# TMC2660_driver.net
KiCad netlist of a schematic drawn in Altium Designer
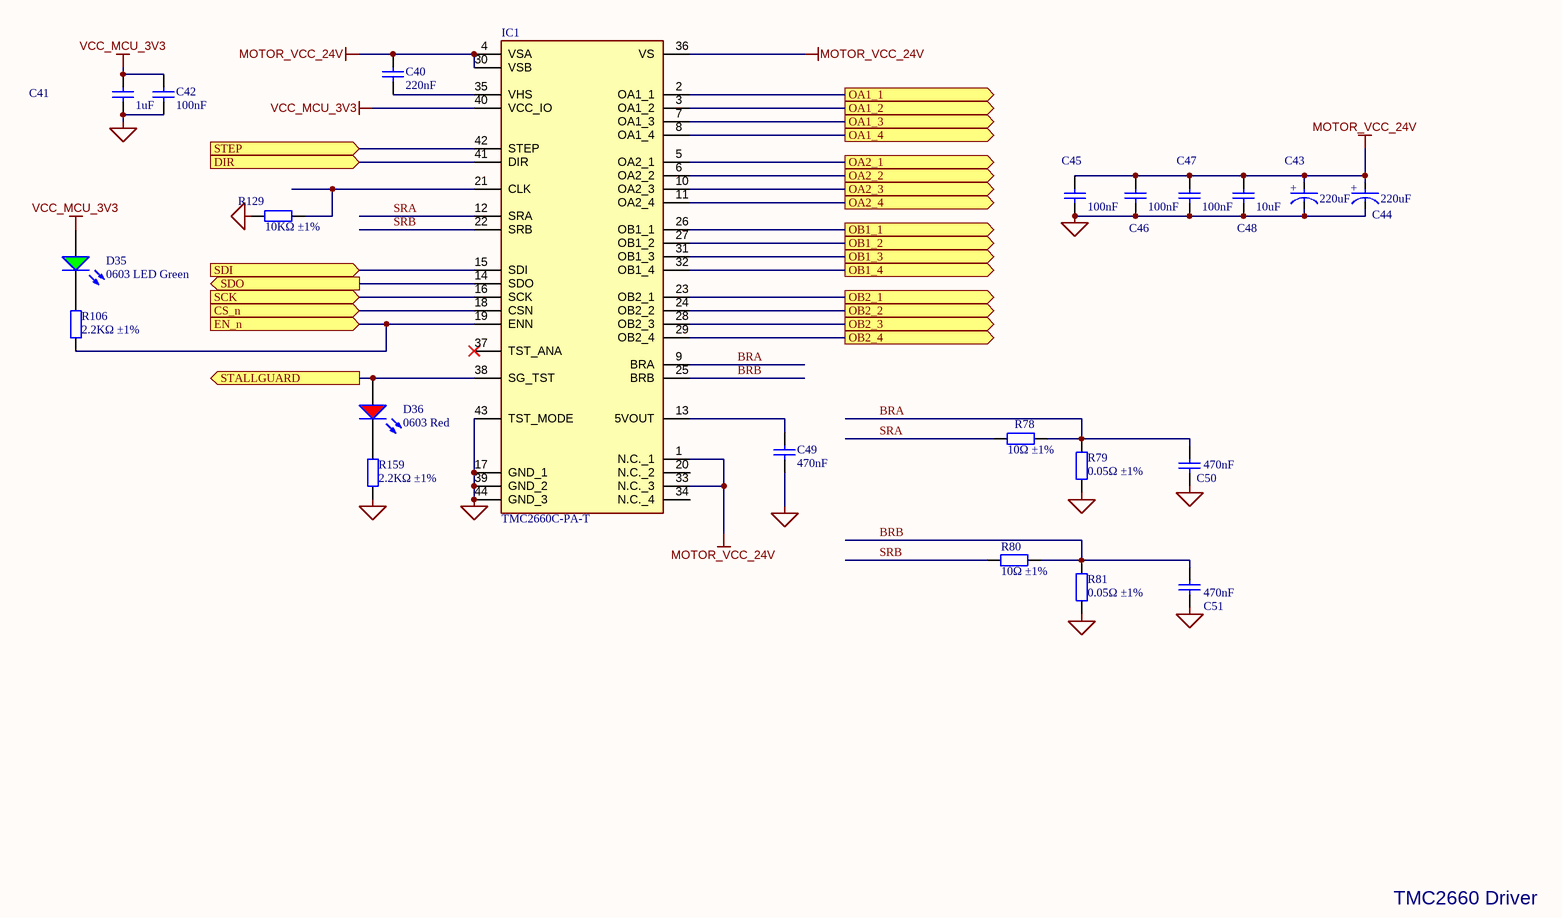
[diagram p0: TMC2660_driver.SchDoc]

(export (version "E")
  (design (tool "Eeschema 10.0.6"))
  (components
    (comp (ref "C40")
      (value "220nF")
      (footprint "0603_C")
      (description "Chip capacitors")
      (fields
        (field (name "MANUFACTURER") "Samsung Electro-Mechanics")
        (field (name "MANUFACTURER PART NUMBER") "CL10B224KA8NNNC")
      )
      (libsource (lib "Cap") (part "0603 220nF (224) 10% 25V"))
    )
    (comp (ref "C41")
      (value "1uF")
      (footprint "0603_C")
      (description "Chip capacitors")
      (fields
        (field (name "MANUFACTURER") "Samsung Electro-Mechanics")
        (field (name "MANUFACTURER PART NUMBER") "CL10A105KB8NNNC")
      )
      (libsource (lib "Cap") (part "0603 1uF (105) 10% 50V"))
    )
    (comp (ref "C42")
      (value "100nF")
      (footprint "0603_C")
      (description "50V 100nF X7R ±10% 0603 Multilayer Ceramic Capacitors MLCC - SMD/SMT ROHS")
      (fields
        (field (name "MANUFACTURER") "YAGEO")
        (field (name "MANUFACTURER PART NUMBER") "CC0603KRX7R9BB104")
      )
      (libsource (lib "Sienci_Labs") (part "0603 100nF (104) 10% 50V"))
    )
    (comp (ref "C43")
      (value "220uF")
      (footprint "FP-FKG-MFG")
      (description "CAP ALUM 220UF 20% 50V SMD")
      (fields (field (name "TOLERANCE") "20%") (field (name "MANUFACTURER") "Nichicon"))
      (libsource (lib "Universal_CNC_Breakout") (part "UUD1H221MNL1GS"))
    )
    (comp (ref "C44")
      (value "220uF")
      (footprint "FP-FKG-MFG")
      (description "CAP ALUM 220UF 20% 50V SMD")
      (fields (field (name "TOLERANCE") "20%") (field (name "MANUFACTURER") "Nichicon"))
      (libsource (lib "Universal_CNC_Breakout") (part "UUD1H221MNL1GS"))
    )
    (comp (ref "C45")
      (value "100nF")
      (footprint "0603_C")
      (description "50V 100nF X7R ±10% 0603 Multilayer Ceramic Capacitors MLCC - SMD/SMT ROHS")
      (fields
        (field (name "MANUFACTURER") "YAGEO")
        (field (name "MANUFACTURER PART NUMBER") "CC0603KRX7R9BB104")
      )
      (libsource (lib "Sienci_Labs") (part "0603 100nF (104) 10% 50V"))
    )
    (comp (ref "C46")
      (value "100nF")
      (footprint "0603_C")
      (description "50V 100nF X7R ±10% 0603 Multilayer Ceramic Capacitors MLCC - SMD/SMT ROHS")
      (fields
        (field (name "MANUFACTURER") "YAGEO")
        (field (name "MANUFACTURER PART NUMBER") "CC0603KRX7R9BB104")
      )
      (libsource (lib "Sienci_Labs") (part "0603 100nF (104) 10% 50V"))
    )
    (comp (ref "C47")
      (value "100nF")
      (footprint "0603_C")
      (description "50V 100nF X7R ±10% 0603 Multilayer Ceramic Capacitors MLCC - SMD/SMT ROHS")
      (fields
        (field (name "MANUFACTURER") "YAGEO")
        (field (name "MANUFACTURER PART NUMBER") "CC0603KRX7R9BB104")
      )
      (libsource (lib "Sienci_Labs") (part "0603 100nF (104) 10% 50V"))
    )
    (comp (ref "C48")
      (value "10uF")
      (footprint "0805_C")
      (description "Chip capacitors")
      (fields
        (field (name "MANUFACTURER") "Samsung Electro-Mechanics")
        (field (name "MANUFACTURER PART NUMBER") "CL21A106KAYNNNE")
      )
      (libsource (lib "Cap") (part "0805 10uF (106) 10% 25V"))
    )
    (comp (ref "C49")
      (value "470nF")
      (footprint "0603_C")
      (description "Chip capacitors")
      (fields
        (field (name "MANUFACTURER") "Samsung Electro-Mechanics")
        (field (name "MANUFACTURER PART NUMBER") "CL10B474KA8NNNC")
      )
      (libsource (lib "Cap") (part "0603 470nF (474) 10% 25V"))
    )
    (comp (ref "C50")
      (value "470nF")
      (footprint "0603_C")
      (description "Chip capacitors")
      (fields (field (name "MANUFACTURER") "Samsung Electro-Mechanics") (field (name "TOLERANCE") "10%"))
      (libsource (lib "Sienci_Labs") (part "0603 470nF (474) 10% 25V"))
    )
    (comp (ref "C51")
      (value "470nF")
      (footprint "0603_C")
      (description "Chip capacitors")
      (fields (field (name "MANUFACTURER") "Samsung Electro-Mechanics") (field (name "TOLERANCE") "10%"))
      (libsource (lib "Sienci_Labs") (part "0603 470nF (474) 10% 25V"))
    )
    (comp (ref "D35")
      (value "0603 LED Green")
      (footprint "0603_LED_S1 - GREEN")
      (fields
        (field (name "MANUFACTURER PART NUMBER") "19-217/GHC-YR1S2/3T")
        (field (name "MANUFACTURER") "Everlight Elec")
      )
      (libsource (lib "Sienci_Labs") (part "19-217/GHC-YR1S2/3T"))
    )
    (comp (ref "D36")
      (value "0603 Red")
      (footprint "0603_LED_S1")
      (fields
        (field (name "MANUFACTURER") "Everlight Elec")
        (field (name "MANUFACTURER PART NUMBER") "19-213SURC/S530-A3/TR8")
      )
      (libsource (lib "Sienci_Labs") (part "19-213SURC/S530-A3/TR8"))
    )
    (comp (ref "IC1")
      (value "TMC2660C-PA-T")
      (footprint "QFP80P1200X1200X160-44N")
      (description "QFP-44 Motor Driver ICs ROHS")
      (fields (field (name "MANUFACTURER") "TRINAMIC"))
      (libsource (lib "Sienci_Labs") (part "TMC2660C-PA-T"))
    )
    (comp (ref "R78")
      (value "10Ω ±1%")
      (footprint "0603_R")
      (description "Chip resistor")
      (fields
        (field (name "MANUFACTURER") "Uniroyal Elec")
        (field (name "MANUFACTURER PART NUMBER") "0603WAF100JT5E")
      )
      (libsource (lib "RES") (part "0603 10R (10R0) 1%"))
    )
    (comp (ref "R79")
      (value "0.05Ω ±1%")
      (footprint "1206_R")
      (description "1W ±100ppm/℃ ±1% 50mΩ 1206 Chip Resistor - Surface Mount ROHS")
      (fields (field (name "MANUFACTURER") "YAGEO") (field (name "POWER") "1W"))
      (libsource (lib "Sienci_Labs") (part "1206 0.05R (R50) 1%"))
    )
    (comp (ref "R80")
      (value "10Ω ±1%")
      (footprint "0603_R")
      (description "Chip resistor")
      (fields
        (field (name "MANUFACTURER") "Uniroyal Elec")
        (field (name "MANUFACTURER PART NUMBER") "0603WAF100JT5E")
      )
      (libsource (lib "RES") (part "0603 10R (10R0) 1%"))
    )
    (comp (ref "R81")
      (value "0.05Ω ±1%")
      (footprint "1206_R")
      (description "1W ±100ppm/℃ ±1% 50mΩ 1206 Chip Resistor - Surface Mount ROHS")
      (fields (field (name "MANUFACTURER") "YAGEO") (field (name "POWER") "1W"))
      (libsource (lib "Sienci_Labs") (part "1206 0.05R (R50) 1%"))
    )
    (comp (ref "R106")
      (value "2.2KΩ ±1%")
      (footprint "0402_R")
      (description "Chip resistor")
      (fields
        (field (name "MANUFACTURER") "Uniroyal Elec")
        (field (name "MANUFACTURER PART NUMBER") "0402WGF2201TCE")
      )
      (libsource (lib "RES") (part "0402 2.2K (2201) 1%"))
    )
    (comp (ref "R129")
      (value "10KΩ ±1%")
      (footprint "0603_R")
      (description "Chip resistor")
      (fields
        (field (name "MANUFACTURER") "Uniroyal Elec")
        (field (name "MANUFACTURER PART NUMBER") "0603WAF1002T5E")
      )
      (libsource (lib "RES") (part "0603 10K (1002) 1%"))
    )
    (comp (ref "R159")
      (value "2.2KΩ ±1%")
      (footprint "0402_R")
      (description "Chip resistor")
      (fields
        (field (name "MANUFACTURER") "Uniroyal Elec")
        (field (name "MANUFACTURER PART NUMBER") "0402WGF2201TCE")
      )
      (libsource (lib "RES") (part "0402 2.2K (2201) 1%"))
    )
  )
  (nets
    (net (code "1") (name "/BRA") (class "Default")
      (node (ref "C50") (pin "1") (pinfunction "1_1") (pintype "passive"))
      (node (ref "IC1") (pin "9") (pinfunction "BRA_9") (pintype "passive"))
      (node (ref "R78") (pin "2") (pinfunction "2_2") (pintype "passive"))
      (node (ref "R79") (pin "2") (pinfunction "2_2") (pintype "passive"))
    )
    (net (code "2") (name "/BRB") (class "Default")
      (node (ref "C51") (pin "1") (pinfunction "1_1") (pintype "passive"))
      (node (ref "IC1") (pin "25") (pinfunction "BRB_25") (pintype "passive"))
      (node (ref "R80") (pin "2") (pinfunction "2_2") (pintype "passive"))
      (node (ref "R81") (pin "2") (pinfunction "2_2") (pintype "passive"))
    )
    (net (code "3") (name "/CS_n") (class "Default")
      (node (ref "IC1") (pin "18") (pinfunction "CSN_18") (pintype "passive"))
    )
    (net (code "4") (name "/DIR") (class "Default")
      (node (ref "IC1") (pin "41") (pinfunction "DIR_41") (pintype "passive"))
    )
    (net (code "5") (name "/EN_n") (class "Default")
      (node (ref "IC1") (pin "19") (pinfunction "ENN_19") (pintype "passive"))
      (node (ref "R106") (pin "1") (pinfunction "1_1") (pintype "passive"))
    )
    (net (code "6") (name "/OA1_1") (class "Default")
      (node (ref "IC1") (pin "2") (pinfunction "OA1_1_2") (pintype "passive"))
    )
    (net (code "7") (name "/OA1_2") (class "Default")
      (node (ref "IC1") (pin "3") (pinfunction "OA1_2_3") (pintype "passive"))
    )
    (net (code "8") (name "/OA1_3") (class "Default")
      (node (ref "IC1") (pin "7") (pinfunction "OA1_3_7") (pintype "passive"))
    )
    (net (code "9") (name "/OA1_4") (class "Default")
      (node (ref "IC1") (pin "8") (pinfunction "OA1_4_8") (pintype "passive"))
    )
    (net (code "10") (name "/OA2_1") (class "Default")
      (node (ref "IC1") (pin "5") (pinfunction "OA2_1_5") (pintype "passive"))
    )
    (net (code "11") (name "/OA2_2") (class "Default")
      (node (ref "IC1") (pin "6") (pinfunction "OA2_2_6") (pintype "passive"))
    )
    (net (code "12") (name "/OA2_3") (class "Default")
      (node (ref "IC1") (pin "10") (pinfunction "OA2_3_10") (pintype "passive"))
    )
    (net (code "13") (name "/OA2_4") (class "Default")
      (node (ref "IC1") (pin "11") (pinfunction "OA2_4_11") (pintype "passive"))
    )
    (net (code "14") (name "/OB1_1") (class "Default")
      (node (ref "IC1") (pin "26") (pinfunction "OB1_1_26") (pintype "passive"))
    )
    (net (code "15") (name "/OB1_2") (class "Default")
      (node (ref "IC1") (pin "27") (pinfunction "OB1_2_27") (pintype "passive"))
    )
    (net (code "16") (name "/OB1_3") (class "Default")
      (node (ref "IC1") (pin "31") (pinfunction "OB1_3_31") (pintype "passive"))
    )
    (net (code "17") (name "/OB1_4") (class "Default")
      (node (ref "IC1") (pin "32") (pinfunction "OB1_4_32") (pintype "passive"))
    )
    (net (code "18") (name "/OB2_1") (class "Default")
      (node (ref "IC1") (pin "23") (pinfunction "OB2_1_23") (pintype "passive"))
    )
    (net (code "19") (name "/OB2_2") (class "Default")
      (node (ref "IC1") (pin "24") (pinfunction "OB2_2_24") (pintype "passive"))
    )
    (net (code "20") (name "/OB2_3") (class "Default")
      (node (ref "IC1") (pin "28") (pinfunction "OB2_3_28") (pintype "passive"))
    )
    (net (code "21") (name "/OB2_4") (class "Default")
      (node (ref "IC1") (pin "29") (pinfunction "OB2_4_29") (pintype "passive"))
    )
    (net (code "22") (name "/SCK") (class "Default")
      (node (ref "IC1") (pin "16") (pinfunction "SCK_16") (pintype "passive"))
    )
    (net (code "23") (name "/SDI") (class "Default")
      (node (ref "IC1") (pin "15") (pinfunction "SDI_15") (pintype "passive"))
    )
    (net (code "24") (name "/SDO") (class "Default")
      (node (ref "IC1") (pin "14") (pinfunction "SDO_14") (pintype "passive"))
    )
    (net (code "25") (name "/SRA") (class "Default")
      (node (ref "IC1") (pin "12") (pinfunction "SRA_12") (pintype "passive"))
      (node (ref "R78") (pin "1") (pinfunction "1_1") (pintype "passive"))
    )
    (net (code "26") (name "/SRB") (class "Default")
      (node (ref "IC1") (pin "22") (pinfunction "SRB_22") (pintype "passive"))
      (node (ref "R80") (pin "1") (pinfunction "1_1") (pintype "passive"))
    )
    (net (code "27") (name "/STALLGUARD") (class "Default")
      (node (ref "D36") (pin "A") (pinfunction "A_A") (pintype "passive"))
      (node (ref "IC1") (pin "38") (pinfunction "SG_TST_38") (pintype "passive"))
    )
    (net (code "28") (name "/STEP") (class "Default")
      (node (ref "IC1") (pin "42") (pinfunction "STEP_42") (pintype "passive"))
    )
    (net (code "29") (name "MCU_GND") (class "Default")
      (node (ref "C41") (pin "1") (pinfunction "1_1") (pintype "passive"))
      (node (ref "C42") (pin "2") (pinfunction "2_2") (pintype "passive"))
      (node (ref "C43") (pin "1") (pinfunction "C_1") (pintype "passive"))
      (node (ref "C44") (pin "1") (pinfunction "C_1") (pintype "passive"))
      (node (ref "C45") (pin "2") (pinfunction "2_2") (pintype "passive"))
      (node (ref "C46") (pin "2") (pinfunction "2_2") (pintype "passive"))
      (node (ref "C47") (pin "2") (pinfunction "2_2") (pintype "passive"))
      (node (ref "C48") (pin "1") (pinfunction "1_1") (pintype "passive"))
      (node (ref "C49") (pin "1") (pinfunction "1_1") (pintype "passive"))
      (node (ref "C50") (pin "2") (pinfunction "2_2") (pintype "passive"))
      (node (ref "C51") (pin "2") (pinfunction "2_2") (pintype "passive"))
      (node (ref "IC1") (pin "17") (pinfunction "GND_1_17") (pintype "passive"))
      (node (ref "IC1") (pin "39") (pinfunction "GND_2_39") (pintype "passive"))
      (node (ref "IC1") (pin "43") (pinfunction "TST_MODE_43") (pintype "passive"))
      (node (ref "IC1") (pin "44") (pinfunction "GND_3_44") (pintype "passive"))
      (node (ref "R129") (pin "2") (pinfunction "2_2") (pintype "passive"))
      (node (ref "R159") (pin "1") (pinfunction "1_1") (pintype "passive"))
      (node (ref "R79") (pin "1") (pinfunction "1_1") (pintype "passive"))
      (node (ref "R81") (pin "1") (pinfunction "1_1") (pintype "passive"))
    )
    (net (code "30") (name "MOTOR_VCC_24V") (class "Default")
      (node (ref "C40") (pin "2") (pinfunction "2_2") (pintype "passive"))
      (node (ref "C43") (pin "2") (pinfunction "A_2") (pintype "passive"))
      (node (ref "C44") (pin "2") (pinfunction "A_2") (pintype "passive"))
      (node (ref "C45") (pin "1") (pinfunction "1_1") (pintype "passive"))
      (node (ref "C46") (pin "1") (pinfunction "1_1") (pintype "passive"))
      (node (ref "C47") (pin "1") (pinfunction "1_1") (pintype "passive"))
      (node (ref "C48") (pin "2") (pinfunction "2_2") (pintype "passive"))
      (node (ref "IC1") (pin "1") (pinfunction "N.C._1_1") (pintype "passive"))
      (node (ref "IC1") (pin "30") (pinfunction "VSB_30") (pintype "passive"))
      (node (ref "IC1") (pin "33") (pinfunction "N.C._3_33") (pintype "passive"))
      (node (ref "IC1") (pin "36") (pinfunction "VS_36") (pintype "passive"))
      (node (ref "IC1") (pin "4") (pinfunction "VSA_4") (pintype "passive"))
    )
    (net (code "31") (name "Net-(D35-PadK)") (class "Default")
      (node (ref "D35") (pin "K") (pinfunction "K_K") (pintype "passive"))
      (node (ref "R106") (pin "2") (pinfunction "2_2") (pintype "passive"))
    )
    (net (code "32") (name "Net-(D36-PadK)") (class "Default")
      (node (ref "D36") (pin "K") (pinfunction "K_K") (pintype "passive"))
      (node (ref "R159") (pin "2") (pinfunction "2_2") (pintype "passive"))
    )
    (net (code "33") (name "Net-(IC1-5VOUT)") (class "Default")
      (node (ref "C49") (pin "2") (pinfunction "2_2") (pintype "passive"))
      (node (ref "IC1") (pin "13") (pinfunction "5VOUT_13") (pintype "passive"))
    )
    (net (code "34") (name "Net-(IC1-CLK)") (class "Default")
      (node (ref "IC1") (pin "21") (pinfunction "CLK_21") (pintype "passive"))
      (node (ref "R129") (pin "1") (pinfunction "1_1") (pintype "passive"))
    )
    (net (code "35") (name "Net-(IC1-VHS)") (class "Default")
      (node (ref "C40") (pin "1") (pinfunction "1_1") (pintype "passive"))
      (node (ref "IC1") (pin "35") (pinfunction "VHS_35") (pintype "passive"))
    )
    (net (code "36") (name "VCC_MCU_3V3") (class "Default")
      (node (ref "C41") (pin "2") (pinfunction "2_2") (pintype "passive"))
      (node (ref "C42") (pin "1") (pinfunction "1_1") (pintype "passive"))
      (node (ref "D35") (pin "A") (pinfunction "A_A") (pintype "passive"))
      (node (ref "IC1") (pin "40") (pinfunction "VCC_IO_40") (pintype "passive"))
    )
    (net (code "37") (name "unconnected-(IC1-N.C._2-Pad20)") (class "Default")
      (node (ref "IC1") (pin "20") (pinfunction "N.C._2_20") (pintype "passive"))
    )
    (net (code "38") (name "unconnected-(IC1-N.C._4-Pad34)") (class "Default")
      (node (ref "IC1") (pin "34") (pinfunction "N.C._4_34") (pintype "passive"))
    )
    (net (code "39") (name "unconnected-(IC1-TST_ANA-Pad37)") (class "Default")
      (node (ref "IC1") (pin "37") (pinfunction "TST_ANA_37") (pintype "passive+no_connect"))
    )
  )
)
